# SD.net
KiCad netlist of a schematic drawn in Altium Designer
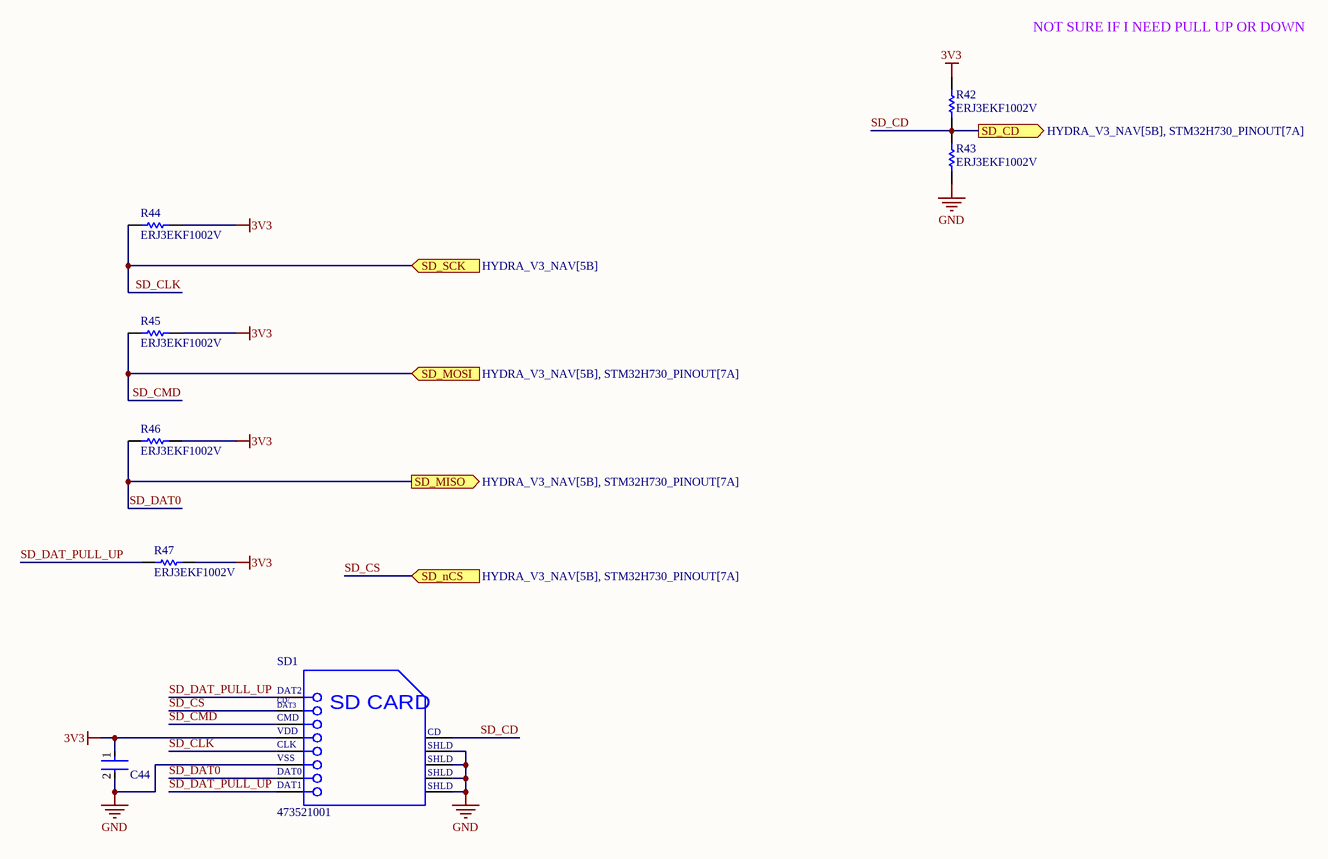
[diagram p0: SD.SchDoc]

(export (version "E")
  (design (tool "Eeschema 10.0.6"))
  (components
    (comp (ref "C44")
      (value "C0402C104K8PACTU")
      (footprint "FP-C0402-BB-MFG")
      (description "CAP CER 0.1UF 10V X5R 0402")
      (fields (field (name "MANUFACTURER") "Kemet") (field (name "TOLERANCE") "0.1"))
      (libsource (lib "Altium Content Vault") (part "b4654b650e69147ec39a6b967a45e02"))
    )
    (comp (ref "R42")
      (value "ERJ3EKF1002V")
      (footprint "RESC1609X55X30LL15T15")
      (description "Chip Resistor, 10 KOhm, +/- 1%, 0.1 W, -55 to 155 degC, 0603 (1608 Metric), RoHS, Tape and Reel")
      (fields (field (name "TOLERANCE") "1%") (field (name "MANUFACTURER") "Panasonic"))
      (libsource (lib "Altium Content Vault") (part "RES-2"))
    )
    (comp (ref "R43")
      (value "ERJ3EKF1002V")
      (footprint "RESC1609X55X30LL15T15")
      (description "Chip Resistor, 10 KOhm, +/- 1%, 0.1 W, -55 to 155 degC, 0603 (1608 Metric), RoHS, Tape and Reel")
      (fields (field (name "TOLERANCE") "1%") (field (name "MANUFACTURER") "Panasonic"))
      (libsource (lib "Altium Content Vault") (part "RES-2"))
    )
    (comp (ref "R44")
      (value "ERJ3EKF1002V")
      (footprint "RESC1609X55X30LL15T15")
      (description "Chip Resistor, 10 KOhm, +/- 1%, 0.1 W, -55 to 155 degC, 0603 (1608 Metric), RoHS, Tape and Reel")
      (fields (field (name "TOLERANCE") "1%") (field (name "MANUFACTURER") "Panasonic"))
      (libsource (lib "Altium Content Vault") (part "RES-2"))
    )
    (comp (ref "R45")
      (value "ERJ3EKF1002V")
      (footprint "RESC1609X55X30LL15T15")
      (description "Chip Resistor, 10 KOhm, +/- 1%, 0.1 W, -55 to 155 degC, 0603 (1608 Metric), RoHS, Tape and Reel")
      (fields (field (name "TOLERANCE") "1%") (field (name "MANUFACTURER") "Panasonic"))
      (libsource (lib "Altium Content Vault") (part "RES-2"))
    )
    (comp (ref "R46")
      (value "ERJ3EKF1002V")
      (footprint "RESC1609X55X30LL15T15")
      (description "Chip Resistor, 10 KOhm, +/- 1%, 0.1 W, -55 to 155 degC, 0603 (1608 Metric), RoHS, Tape and Reel")
      (fields (field (name "TOLERANCE") "1%") (field (name "MANUFACTURER") "Panasonic"))
      (libsource (lib "Altium Content Vault") (part "RES-2"))
    )
    (comp (ref "R47")
      (value "ERJ3EKF1002V")
      (footprint "RESC1609X55X30LL15T15")
      (description "Chip Resistor, 10 KOhm, +/- 1%, 0.1 W, -55 to 155 degC, 0603 (1608 Metric), RoHS, Tape and Reel")
      (fields (field (name "TOLERANCE") "1%") (field (name "MANUFACTURER") "Panasonic"))
      (libsource (lib "Altium Content Vault") (part "RES-2"))
    )
    (comp (ref "SD1")
      (value "473521001")
      (footprint "MOLX-473521001_V")
      (description "MicroSD(TM), Pitch 1.1 mm, 8 Position, Height 1.88 mm, -20 to 85 degC, RoHS, Tape and Reel")
      (fields (field (name "MANUFACTURER") "Molex"))
      (libsource (lib "Altium Content Vault") (part "CN-SD-8-1SW-4S"))
    )
  )
  (nets
    (net (code "1") (name "/SD_CD") (class "Default")
      (node (ref "R42") (pin "1") (pinfunction "1_1") (pintype "passive"))
      (node (ref "R43") (pin "2") (pinfunction "2_2") (pintype "passive"))
      (node (ref "SD1") (pin "9") (pinfunction "CD_9") (pintype "passive"))
    )
    (net (code "2") (name "/SD_CLK") (class "Default")
      (node (ref "R44") (pin "1") (pinfunction "1_1") (pintype "passive"))
      (node (ref "SD1") (pin "5") (pinfunction "CLK_5") (pintype "passive"))
    )
    (net (code "3") (name "/SD_CMD") (class "Default")
      (node (ref "R45") (pin "1") (pinfunction "1_1") (pintype "passive"))
      (node (ref "SD1") (pin "3") (pinfunction "CMD_3") (pintype "passive"))
    )
    (net (code "4") (name "/SD_CS") (class "Default")
      (node (ref "SD1") (pin "2") (pinfunction "CD/DAT3_2") (pintype "passive"))
    )
    (net (code "5") (name "/SD_DAT0") (class "Default")
      (node (ref "R46") (pin "1") (pinfunction "1_1") (pintype "passive"))
      (node (ref "SD1") (pin "7") (pinfunction "DAT0_7") (pintype "passive"))
    )
    (net (code "6") (name "/SD_DAT_PULL_UP") (class "Default")
      (node (ref "R47") (pin "1") (pinfunction "1_1") (pintype "passive"))
      (node (ref "SD1") (pin "1") (pinfunction "DAT2_1") (pintype "passive"))
      (node (ref "SD1") (pin "8") (pinfunction "DAT1_8") (pintype "passive"))
    )
    (net (code "7") (name "3V3") (class "Default")
      (node (ref "C44") (pin "1") (pinfunction "1_1") (pintype "passive"))
      (node (ref "R42") (pin "2") (pinfunction "2_2") (pintype "passive"))
      (node (ref "R44") (pin "2") (pinfunction "2_2") (pintype "passive"))
      (node (ref "R45") (pin "2") (pinfunction "2_2") (pintype "passive"))
      (node (ref "R46") (pin "2") (pinfunction "2_2") (pintype "passive"))
      (node (ref "R47") (pin "2") (pinfunction "2_2") (pintype "passive"))
      (node (ref "SD1") (pin "4") (pinfunction "VDD_4") (pintype "passive"))
    )
    (net (code "8") (name "GND") (class "Default")
      (node (ref "C44") (pin "2") (pinfunction "2_2") (pintype "passive"))
      (node (ref "R43") (pin "1") (pinfunction "1_1") (pintype "passive"))
      (node (ref "SD1") (pin "10") (pinfunction "SHLD_10") (pintype "passive"))
      (node (ref "SD1") (pin "11") (pinfunction "SHLD_11") (pintype "passive"))
      (node (ref "SD1") (pin "12") (pinfunction "SHLD_12") (pintype "passive"))
      (node (ref "SD1") (pin "13") (pinfunction "SHLD_13") (pintype "passive"))
      (node (ref "SD1") (pin "6") (pinfunction "VSS_6") (pintype "passive"))
    )
  )
)
